# stabilizer_current_sense.net
KiCad netlist of a schematic drawn in Altium Designer
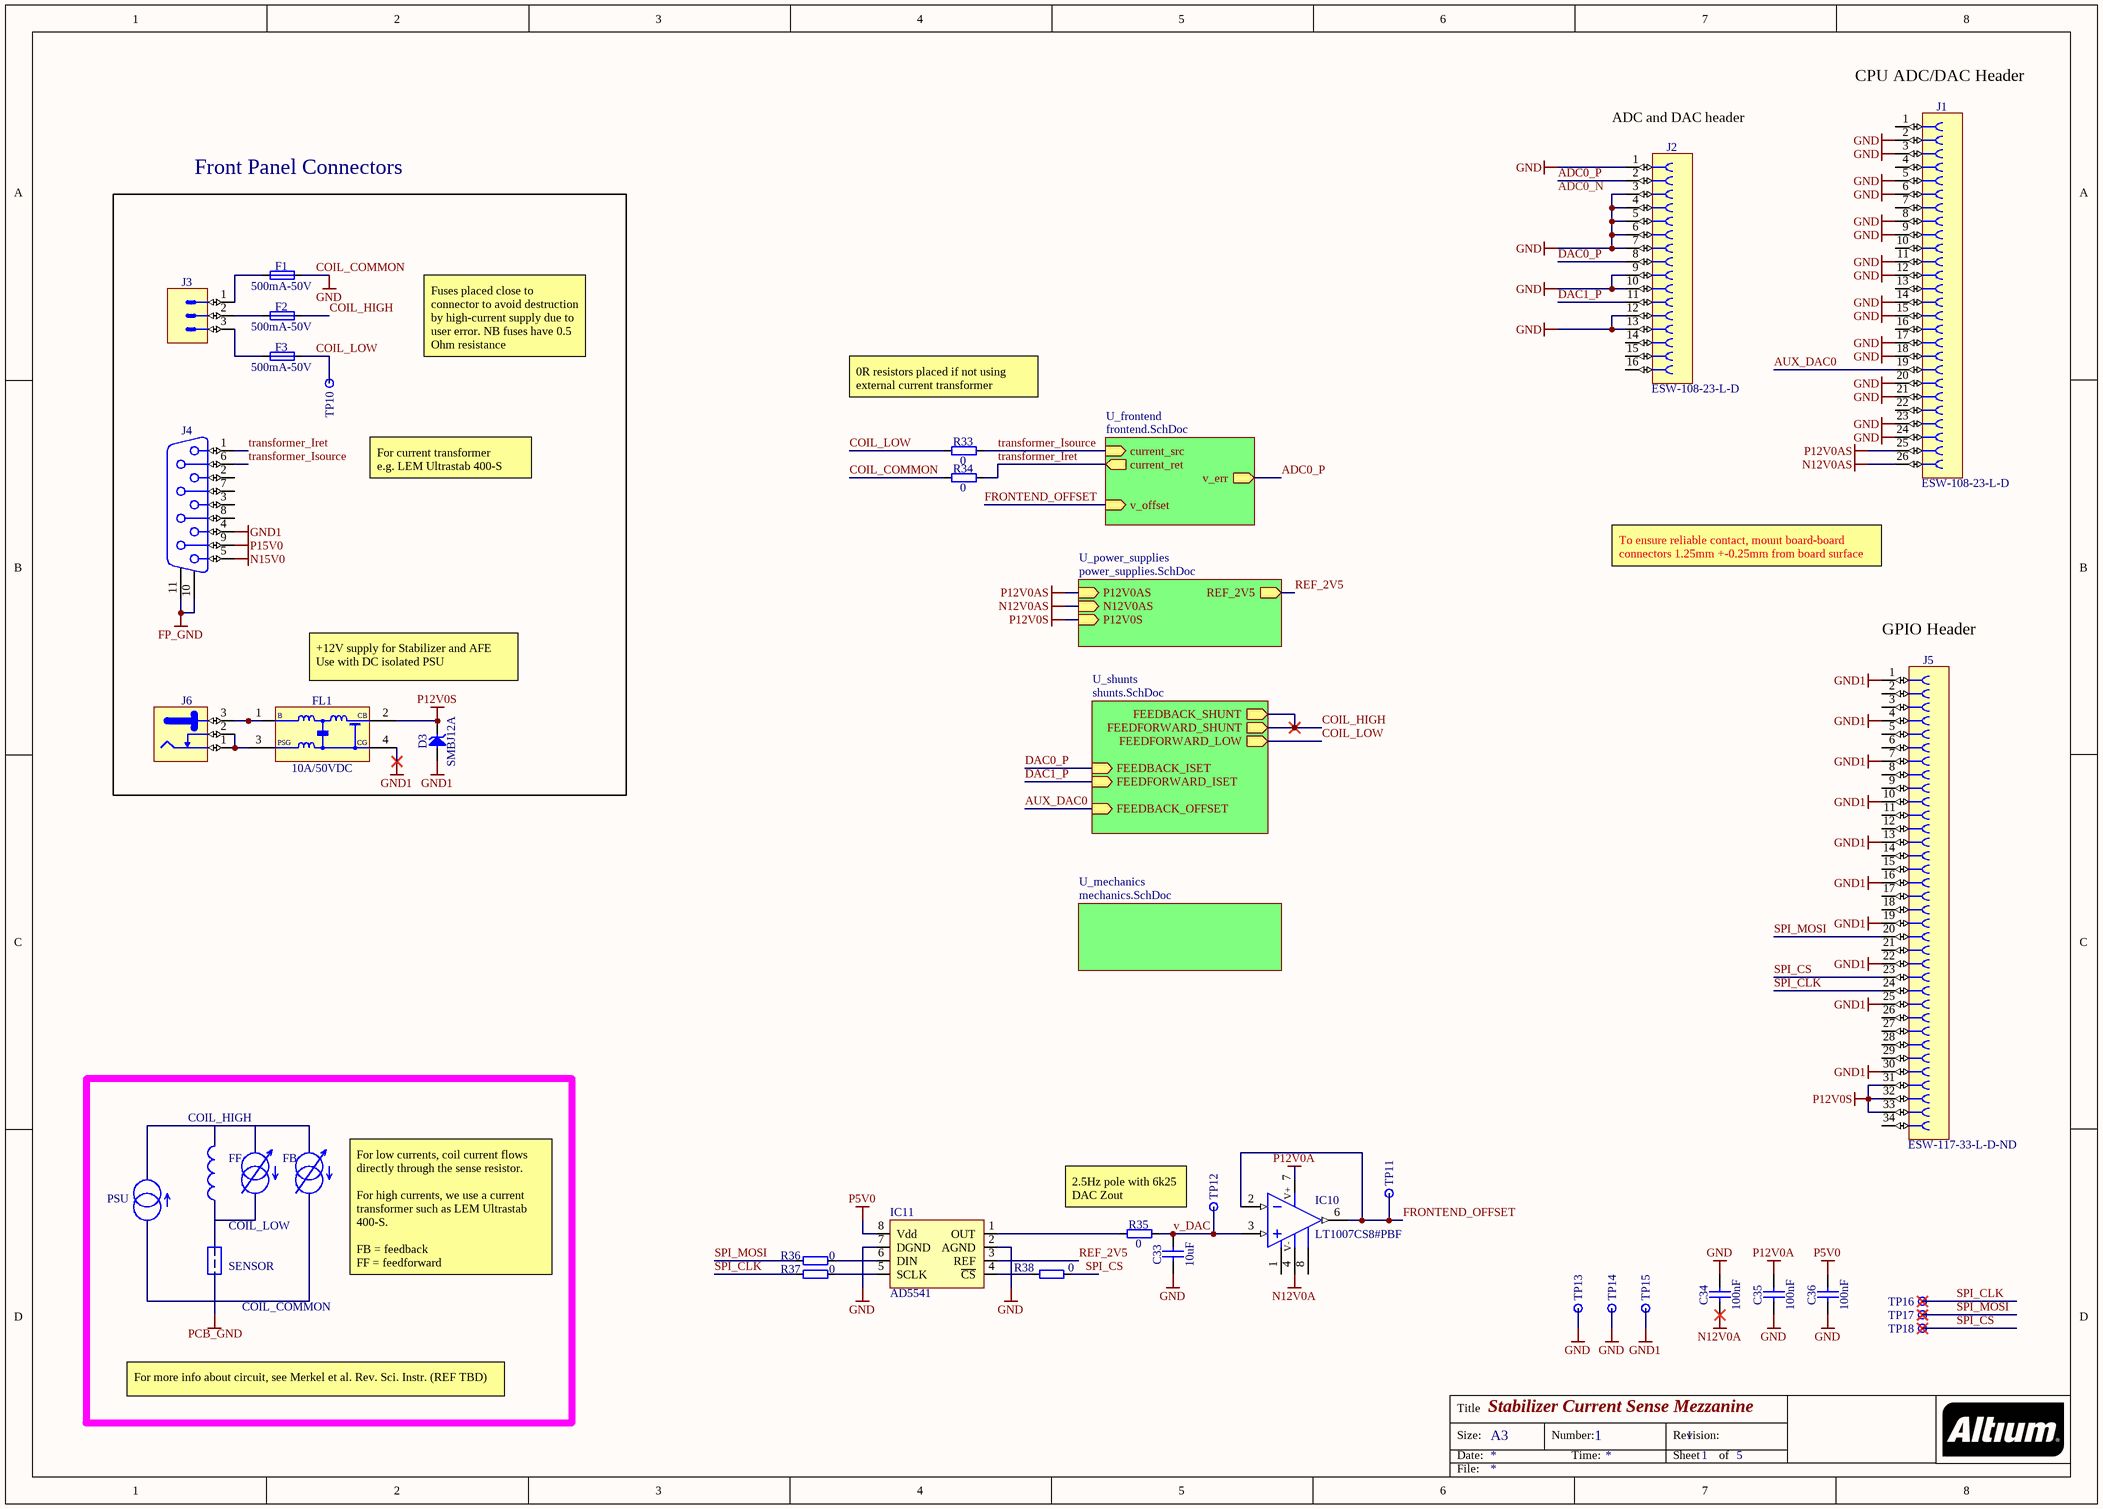
[diagram p0: stabilizer_current_sense.SchDoc]

(export (version "E")
  (design (tool "Eeschema 10.0.6"))
  (components
    (comp (ref "C33")
      (value "10uF")
      (footprint "CAPC2012X95N")
      (description "Non-polarised capacitor")
      (fields
        (field (name "PART NUMBER") "CC0805_10UF_25V_10%_X5R")
        (field (name "VOLTAGE") "25V")
        (field (name "AUTHOR") "CERN DEM JLC")
      )
      (libsource (lib "Capacitors") (part "Capacitor - non polarized"))
    )
    (comp (ref "C34")
      (value "100nF")
      (footprint "CAPC1608X87N")
      (description "Non-polarised capacitor")
      (fields
        (field (name "PART NUMBER") "CC0603_100NF_50V_10%_X7R")
        (field (name "VOLTAGE") "50V")
        (field (name "AUTHOR") "CERN DEM JLC")
      )
      (libsource (lib "Capacitors") (part "Capacitor - non polarized"))
    )
    (comp (ref "C35")
      (value "100nF")
      (footprint "CAPC1608X87N")
      (description "Non-polarised capacitor")
      (fields
        (field (name "PART NUMBER") "CC0603_100NF_50V_10%_X7R")
        (field (name "VOLTAGE") "50V")
        (field (name "AUTHOR") "CERN DEM JLC")
      )
      (libsource (lib "Capacitors") (part "Capacitor - non polarized"))
    )
    (comp (ref "C36")
      (value "100nF")
      (footprint "CAPC1608X87N")
      (description "Non-polarised capacitor")
      (fields
        (field (name "PART NUMBER") "CC0603_100NF_50V_10%_X7R")
        (field (name "VOLTAGE") "50V")
        (field (name "AUTHOR") "CERN DEM JLC")
      )
      (libsource (lib "Capacitors") (part "Capacitor - non polarized"))
    )
    (comp (ref "D3")
      (value "SMBJ12A")
      (footprint "DIOM5336X265N")
      (description "Zener Diode")
      (fields
        (field (name "VOLTAGE") "12V")
        (field (name "POWER") "600W")
        (field (name "AUTHOR") "CERN DEM JLC")
      )
      (libsource (lib "ICs And Semiconductors") (part "Diode Zener"))
    )
    (comp (ref "F1")
      (value "500mA-50V")
      (footprint "FUSC1608X55N")
      (description "Fuse")
      (fields
        (field (name "PART NUMBER") "FUS0603_BOURNS-SF-0603F050-2")
        (field (name "MANUFACTURER") "BOURNS")
        (field (name "AUTHOR") "CERN DEM JLC")
      )
      (libsource (lib "Eletro-mechanical") (part "Fuse"))
    )
    (comp (ref "F2")
      (value "500mA-50V")
      (footprint "FUSC1608X55N")
      (description "Fuse")
      (fields
        (field (name "PART NUMBER") "FUS0603_BOURNS-SF-0603F050-2")
        (field (name "MANUFACTURER") "BOURNS")
        (field (name "AUTHOR") "CERN DEM JLC")
      )
      (libsource (lib "Eletro-mechanical") (part "Fuse"))
    )
    (comp (ref "F3")
      (value "500mA-50V")
      (footprint "FUSC1608X55N")
      (description "Fuse")
      (fields
        (field (name "PART NUMBER") "FUS0603_BOURNS-SF-0603F050-2")
        (field (name "MANUFACTURER") "BOURNS")
        (field (name "AUTHOR") "CERN DEM JLC")
      )
      (libsource (lib "Eletro-mechanical") (part "Fuse"))
    )
    (comp (ref "FL1")
      (value "10A/50VDC")
      (footprint "FIL_MURATA_BNX02")
      (description "Block Type EMIFIL (LC Combined)")
      (fields
        (field (name "PART NUMBER") "FIL_MURATA_BNX022-01L")
        (field (name "MANUFACTURER") "MURATA")
        (field (name "AUTHOR") "CERN DEM JLC")
      )
      (libsource (lib "Inductors & Transformers") (part "FIL_MURATA_BNX02"))
    )
    (comp (ref "IC10")
      (value "LT1007CS8#PBF")
      (footprint "SOIC127P600X175-8N")
      (description "Operational Amplifier with Offset 1-8")
      (fields (field (name "MANUFACTURER") "LINEAR TECHNOLOGY") (field (name "AUTHOR") "CERN DEM JLC"))
      (libsource (lib "ICs And Semiconductors") (part "Operational Amplifier Type3"))
    )
    (comp (ref "IC11")
      (value "AD5541")
      (footprint "library_ICs:so-8")
      (description "16 bit serial DAC")
      (fields
        (field (name "MANUFACTURER") "ANALOG DEVICES")
        (field (name "MANUFACTURER PART NUMBER") "AD5541LRZ")
      )
      (libsource (lib "LIBRARY_SCH") (part "AD5541LRZ"))
    )
    (comp (ref "J1")
      (value "ESW-108-23-L-D")
      (footprint "connectors:ESW-113-23-L-D")
      (description "Connector Elevated Socket 26 POS 2.54mm, 13.59mm height")
      (fields
        (field (name "MANUFACTURER") "Samtec")
        (field (name "MANUFACTURER PART NUMBER") "ESW-108-23-L-D")
      )
      (libsource (lib "connectors") (part "ESW-113-23-L-D"))
    )
    (comp (ref "J2")
      (value "ESW-108-23-L-D")
      (footprint "connectors:ESW-108-23-L-D")
      (description "Connector Elevated Socket 16 POS 2.54mm, 13.59mm height")
      (fields
        (field (name "MANUFACTURER") "Samtec")
        (field (name "MANUFACTURER PART NUMBER") "ESW-108-23-L-D")
      )
      (libsource (lib "connectors") (part "ESW-108-23-L-D"))
    )
    (comp (ref "J3")
      (value "MSTBA")
      (footprint "PHOENIX_1757255")
      (description "Connector 3 Male")
      (fields
        (field (name "PART NUMBER") "PHOENIX_1757255")
        (field (name "MANUFACTURER") "PHOENIX CONTACT")
        (field (name "AUTHOR") "CERN DEM JLC")
      )
      (libsource (lib "Connectors") (part "Connector 3 Male"))
    )
    (comp (ref "J4")
      (value "D-Sub 9F")
      (footprint "FCI_D09S13A4GV00LF")
      (description "Connector D-sub 9 Female")
      (fields
        (field (name "PART NUMBER") "FCI_D09S13A4GV00LF")
        (field (name "MANUFACTURER") "FCI")
        (field (name "AUTHOR") "CERN DEM JLC")
      )
      (libsource (lib "Connectors") (part "Connector D-sub 9 Female"))
    )
    (comp (ref "J5")
      (value "ESW-108-23-L-D")
      (footprint "connectors:ESW-117-23-L-D")
      (description "Connector Elevated Socket 34 POS 2.54mm, 13.59mm height")
      (fields
        (field (name "MANUFACTURER") "Samtec")
        (field (name "MANUFACTURER PART NUMBER") "ESW-117-33-L-D-ND")
      )
      (libsource (lib "connectors") (part "ESW-117-23-L-D"))
    )
    (comp (ref "J6")
      (value "Jack")
      (footprint "Library-connectors:SWITCHCRAFT_L712RA")
      (description "24V /3. 5A, 2.1mm Diameter Pin, SMD DC Power Supply Connector With  Break Contact")
      (fields
        (field (name "PART NUMBER") "SWITCHCRAFT_L712RA")
        (field (name "MANUFACTURER") "SWITCHCRAFT")
        (field (name "AUTHOR") "GK")
      )
      (libsource (lib "LIBRARY_SCH") (part "CON_DC_5A_THT_RA"))
    )
    (comp (ref "R33")
      (value "0")
      (footprint "RESC1608X55N")
      (description "Resistor")
      (fields
        (field (name "PART NUMBER") "R0603_0R_JUMPER")
        (field (name "MANUFACTURER") "GENERIC")
        (field (name "AUTHOR") "CERN DEM JLC")
      )
      (libsource (lib "Resistors") (part "Resistor"))
    )
    (comp (ref "R34")
      (value "0")
      (footprint "RESC1608X55N")
      (description "Resistor")
      (fields
        (field (name "PART NUMBER") "R0603_0R_JUMPER")
        (field (name "MANUFACTURER") "GENERIC")
        (field (name "AUTHOR") "CERN DEM JLC")
      )
      (libsource (lib "Resistors") (part "Resistor"))
    )
    (comp (ref "R35")
      (value "0")
      (footprint "RESC1608X55N")
      (description "Resistor")
      (fields
        (field (name "PART NUMBER") "R0603_0R_JUMPER")
        (field (name "MANUFACTURER") "GENERIC")
        (field (name "AUTHOR") "CERN DEM JLC")
      )
      (libsource (lib "Resistors") (part "Resistor"))
    )
    (comp (ref "R36")
      (value "0")
      (footprint "RESC1608X55N")
      (description "Resistor")
      (fields
        (field (name "PART NUMBER") "R0603_0R_JUMPER")
        (field (name "MANUFACTURER") "GENERIC")
        (field (name "AUTHOR") "CERN DEM JLC")
      )
      (libsource (lib "Resistors") (part "Resistor"))
    )
    (comp (ref "R37")
      (value "0")
      (footprint "RESC1608X55N")
      (description "Resistor")
      (fields
        (field (name "PART NUMBER") "R0603_0R_JUMPER")
        (field (name "MANUFACTURER") "GENERIC")
        (field (name "AUTHOR") "CERN DEM JLC")
      )
      (libsource (lib "Resistors") (part "Resistor"))
    )
    (comp (ref "R38")
      (value "0")
      (footprint "RESC1608X55N")
      (description "Resistor")
      (fields
        (field (name "PART NUMBER") "R0603_0R_JUMPER")
        (field (name "MANUFACTURER") "GENERIC")
        (field (name "AUTHOR") "CERN DEM JLC")
      )
      (libsource (lib "Resistors") (part "Resistor"))
    )
    (comp (ref "TP10")
      (value "Test Point")
      (footprint "TPS127")
      (fields (field (name "PART NUMBER") "SMD_PAD_1.27X1.27MM") (field (name "AUTHOR") "CERN DEM JLC"))
      (libsource (lib "Eletro-mechanical") (part "Test Point"))
    )
    (comp (ref "TP11")
      (value "Test Point")
      (footprint "TPS127")
      (fields (field (name "PART NUMBER") "SMD_PAD_1.27X1.27MM") (field (name "AUTHOR") "CERN DEM JLC"))
      (libsource (lib "Eletro-mechanical") (part "Test Point"))
    )
    (comp (ref "TP12")
      (value "Test Point")
      (footprint "TPS127")
      (fields (field (name "PART NUMBER") "SMD_PAD_1.27X1.27MM") (field (name "AUTHOR") "CERN DEM JLC"))
      (libsource (lib "Eletro-mechanical") (part "Test Point"))
    )
    (comp (ref "TP13")
      (value "Test Point")
      (footprint "TPS127")
      (fields (field (name "PART NUMBER") "SMD_PAD_1.27X1.27MM") (field (name "AUTHOR") "CERN DEM JLC"))
      (libsource (lib "Eletro-mechanical") (part "Test Point"))
    )
    (comp (ref "TP14")
      (value "Test Point")
      (footprint "TPS127")
      (fields (field (name "PART NUMBER") "SMD_PAD_1.27X1.27MM") (field (name "AUTHOR") "CERN DEM JLC"))
      (libsource (lib "Eletro-mechanical") (part "Test Point"))
    )
    (comp (ref "TP15")
      (value "Test Point")
      (footprint "TPS127")
      (fields (field (name "PART NUMBER") "SMD_PAD_1.27X1.27MM") (field (name "AUTHOR") "CERN DEM JLC"))
      (libsource (lib "Eletro-mechanical") (part "Test Point"))
    )
    (comp (ref "TP16")
      (value "Test Point")
      (footprint "TPS127")
      (fields (field (name "PART NUMBER") "SMD_PAD_1.27X1.27MM") (field (name "AUTHOR") "CERN DEM JLC"))
      (libsource (lib "Eletro-mechanical") (part "Test Point"))
    )
    (comp (ref "TP17")
      (value "Test Point")
      (footprint "TPS127")
      (fields (field (name "PART NUMBER") "SMD_PAD_1.27X1.27MM") (field (name "AUTHOR") "CERN DEM JLC"))
      (libsource (lib "Eletro-mechanical") (part "Test Point"))
    )
    (comp (ref "TP18")
      (value "Test Point")
      (footprint "TPS127")
      (fields (field (name "PART NUMBER") "SMD_PAD_1.27X1.27MM") (field (name "AUTHOR") "CERN DEM JLC"))
      (libsource (lib "Eletro-mechanical") (part "Test Point"))
    )
  )
  (nets
    (net (code "1") (name "/ADC0_P") (class "Default")
      (node (ref "J2") (pin "2") (pinfunction "2_2") (pintype "bidirectional"))
    )
    (net (code "2") (name "/AUX_DAC0") (class "Default")
      (node (ref "J1") (pin "19") (pinfunction "19_19") (pintype "bidirectional"))
    )
    (net (code "3") (name "/COIL_HIGH") (class "Default")
      (node (ref "F2") (pin "1") (pinfunction "1_1") (pintype "passive+no_connect"))
    )
    (net (code "4") (name "/COIL_LOW") (class "Default")
      (node (ref "F3") (pin "1") (pinfunction "1_1") (pintype "passive"))
      (node (ref "R33") (pin "1") (pinfunction "1_1") (pintype "passive"))
      (node (ref "TP10") (pin "1") (pinfunction "1_1") (pintype "bidirectional"))
    )
    (net (code "5") (name "/DAC0_P") (class "Default")
      (node (ref "J2") (pin "8") (pinfunction "8_8") (pintype "bidirectional"))
    )
    (net (code "6") (name "/DAC1_P") (class "Default")
      (node (ref "J2") (pin "11") (pinfunction "11_11") (pintype "bidirectional"))
    )
    (net (code "7") (name "/FRONTEND_OFFSET") (class "Default")
      (node (ref "IC10") (pin "2") (pinfunction "IN-_2") (pintype "input"))
      (node (ref "IC10") (pin "6") (pinfunction "OUT_6") (pintype "output"))
      (node (ref "TP11") (pin "1") (pinfunction "1_1") (pintype "bidirectional"))
    )
    (net (code "8") (name "/REF_2V5") (class "Default")
      (node (ref "IC11") (pin "3") (pinfunction "REF_3") (pintype "passive"))
    )
    (net (code "9") (name "/SPI_CLK") (class "Default")
      (node (ref "J5") (pin "24") (pinfunction "24_24") (pintype "bidirectional"))
      (node (ref "R37") (pin "1") (pinfunction "1_1") (pintype "passive"))
      (node (ref "TP16") (pin "1") (pinfunction "1_1") (pintype "bidirectional"))
    )
    (net (code "10") (name "/SPI_CS") (class "Default")
      (node (ref "J5") (pin "23") (pinfunction "23_23") (pintype "bidirectional"))
      (node (ref "R38") (pin "2") (pinfunction "2_2") (pintype "passive"))
      (node (ref "TP18") (pin "1") (pinfunction "1_1") (pintype "bidirectional"))
    )
    (net (code "11") (name "/SPI_MOSI") (class "Default")
      (node (ref "J5") (pin "20") (pinfunction "20_20") (pintype "bidirectional"))
      (node (ref "R36") (pin "1") (pinfunction "1_1") (pintype "passive"))
      (node (ref "TP17") (pin "1") (pinfunction "1_1") (pintype "bidirectional"))
    )
    (net (code "12") (name "/transformer_Iret") (class "Default")
      (node (ref "J4") (pin "1") (pinfunction "1_1") (pintype "bidirectional"))
      (node (ref "R34") (pin "2") (pinfunction "2_2") (pintype "passive"))
    )
    (net (code "13") (name "/transformer_Isource") (class "Default")
      (node (ref "J4") (pin "6") (pinfunction "6_6") (pintype "bidirectional"))
      (node (ref "R33") (pin "2") (pinfunction "2_2") (pintype "passive"))
    )
    (net (code "14") (name "/v_DAC") (class "Default")
      (node (ref "C33") (pin "2") (pinfunction "2_2") (pintype "passive"))
      (node (ref "IC10") (pin "3") (pinfunction "IN+_3") (pintype "input"))
      (node (ref "R35") (pin "2") (pinfunction "2_2") (pintype "passive"))
      (node (ref "TP12") (pin "1") (pinfunction "1_1") (pintype "bidirectional"))
    )
    (net (code "15") (name "FP_GND") (class "Default")
      (node (ref "J4") (pin "10") (pinfunction "10_10") (pintype "passive"))
      (node (ref "J4") (pin "11") (pinfunction "11_11") (pintype "passive"))
    )
    (net (code "16") (name "GND") (class "Default")
      (node (ref "C33") (pin "1") (pinfunction "1_1") (pintype "passive"))
      (node (ref "C34") (pin "2") (pinfunction "2_2") (pintype "passive"))
      (node (ref "C35") (pin "1") (pinfunction "1_1") (pintype "passive"))
      (node (ref "C36") (pin "1") (pinfunction "1_1") (pintype "passive"))
      (node (ref "F1") (pin "1") (pinfunction "1_1") (pintype "passive"))
      (node (ref "IC11") (pin "2") (pinfunction "AGND_2") (pintype "passive"))
      (node (ref "IC11") (pin "7") (pinfunction "DGND_7") (pintype "passive"))
      (node (ref "J1") (pin "11") (pinfunction "11_11") (pintype "bidirectional"))
      (node (ref "J1") (pin "12") (pinfunction "12_12") (pintype "bidirectional"))
      (node (ref "J1") (pin "14") (pinfunction "14_14") (pintype "bidirectional"))
      (node (ref "J1") (pin "15") (pinfunction "15_15") (pintype "bidirectional"))
      (node (ref "J1") (pin "17") (pinfunction "17_17") (pintype "bidirectional"))
      (node (ref "J1") (pin "18") (pinfunction "18_18") (pintype "bidirectional"))
      (node (ref "J1") (pin "2") (pinfunction "2_2") (pintype "bidirectional"))
      (node (ref "J1") (pin "20") (pinfunction "20_20") (pintype "bidirectional"))
      (node (ref "J1") (pin "21") (pinfunction "21_21") (pintype "bidirectional"))
      (node (ref "J1") (pin "23") (pinfunction "23_23") (pintype "bidirectional"))
      (node (ref "J1") (pin "24") (pinfunction "24_24") (pintype "bidirectional"))
      (node (ref "J1") (pin "3") (pinfunction "3_3") (pintype "bidirectional"))
      (node (ref "J1") (pin "5") (pinfunction "5_5") (pintype "bidirectional"))
      (node (ref "J1") (pin "6") (pinfunction "6_6") (pintype "bidirectional"))
      (node (ref "J1") (pin "8") (pinfunction "8_8") (pintype "bidirectional"))
      (node (ref "J1") (pin "9") (pinfunction "9_9") (pintype "bidirectional"))
      (node (ref "J2") (pin "1") (pinfunction "1_1") (pintype "bidirectional"))
      (node (ref "J2") (pin "10") (pinfunction "10_10") (pintype "bidirectional"))
      (node (ref "J2") (pin "12") (pinfunction "12_12") (pintype "bidirectional"))
      (node (ref "J2") (pin "13") (pinfunction "13_13") (pintype "bidirectional"))
      (node (ref "J2") (pin "3") (pinfunction "3_3") (pintype "bidirectional"))
      (node (ref "J2") (pin "4") (pinfunction "4_4") (pintype "bidirectional"))
      (node (ref "J2") (pin "5") (pinfunction "5_5") (pintype "bidirectional"))
      (node (ref "J2") (pin "6") (pinfunction "6_6") (pintype "bidirectional"))
      (node (ref "J2") (pin "7") (pinfunction "7_7") (pintype "bidirectional"))
      (node (ref "J2") (pin "9") (pinfunction "9_9") (pintype "bidirectional"))
      (node (ref "R34") (pin "1") (pinfunction "1_1") (pintype "passive"))
      (node (ref "TP13") (pin "1") (pinfunction "1_1") (pintype "bidirectional"))
      (node (ref "TP14") (pin "1") (pinfunction "1_1") (pintype "bidirectional"))
    )
    (net (code "17") (name "GND1") (class "Default")
      (node (ref "D3") (pin "2") (pinfunction "A_2") (pintype "passive"))
      (node (ref "FL1") (pin "4") (pinfunction "CG_4") (pintype "passive"))
      (node (ref "J4") (pin "4") (pinfunction "4_4") (pintype "bidirectional"))
      (node (ref "J5") (pin "1") (pinfunction "1_1") (pintype "bidirectional"))
      (node (ref "J5") (pin "10") (pinfunction "10_10") (pintype "bidirectional"))
      (node (ref "J5") (pin "13") (pinfunction "13_13") (pintype "bidirectional"))
      (node (ref "J5") (pin "16") (pinfunction "16_16") (pintype "bidirectional"))
      (node (ref "J5") (pin "19") (pinfunction "19_19") (pintype "bidirectional"))
      (node (ref "J5") (pin "22") (pinfunction "22_22") (pintype "bidirectional"))
      (node (ref "J5") (pin "25") (pinfunction "25_25") (pintype "bidirectional"))
      (node (ref "J5") (pin "30") (pinfunction "30_30") (pintype "bidirectional"))
      (node (ref "J5") (pin "4") (pinfunction "4_4") (pintype "bidirectional"))
      (node (ref "J5") (pin "7") (pinfunction "7_7") (pintype "bidirectional"))
      (node (ref "TP15") (pin "1") (pinfunction "1_1") (pintype "bidirectional"))
    )
    (net (code "18") (name "N12V0A") (class "Default")
      (node (ref "C34") (pin "1") (pinfunction "1_1") (pintype "passive"))
      (node (ref "IC10") (pin "4") (pinfunction "V-_4") (pintype "power_in"))
    )
    (net (code "19") (name "N12V0AS") (class "Default")
      (node (ref "J1") (pin "26") (pinfunction "26_26") (pintype "bidirectional"))
    )
    (net (code "20") (name "N15V0") (class "Default")
      (node (ref "J4") (pin "5") (pinfunction "5_5") (pintype "bidirectional"))
    )
    (net (code "21") (name "Net-(F1-Pad2)") (class "Default")
      (node (ref "F1") (pin "2") (pinfunction "2_2") (pintype "passive"))
      (node (ref "J3") (pin "1") (pinfunction "1_1") (pintype "bidirectional"))
    )
    (net (code "22") (name "Net-(F2-Pad2)") (class "Default")
      (node (ref "F2") (pin "2") (pinfunction "2_2") (pintype "passive"))
      (node (ref "J3") (pin "2") (pinfunction "2_2") (pintype "bidirectional"))
    )
    (net (code "23") (name "Net-(F3-Pad2)") (class "Default")
      (node (ref "F3") (pin "2") (pinfunction "2_2") (pintype "passive"))
      (node (ref "J3") (pin "3") (pinfunction "3_3") (pintype "bidirectional"))
    )
    (net (code "24") (name "Net-(FL1-B)") (class "Default")
      (node (ref "FL1") (pin "1") (pinfunction "B_1") (pintype "passive"))
      (node (ref "J6") (pin "3") (pinfunction "3_3") (pintype "bidirectional"))
    )
    (net (code "25") (name "Net-(FL1-PSG)") (class "Default")
      (node (ref "FL1") (pin "3") (pinfunction "PSG_3") (pintype "passive"))
      (node (ref "J6") (pin "1") (pinfunction "1_1") (pintype "bidirectional"))
      (node (ref "J6") (pin "2") (pinfunction "2_2") (pintype "bidirectional"))
    )
    (net (code "26") (name "Net-(IC11-DIN)") (class "Default")
      (node (ref "IC11") (pin "6") (pinfunction "DIN_6") (pintype "passive"))
      (node (ref "R36") (pin "2") (pinfunction "2_2") (pintype "passive"))
    )
    (net (code "27") (name "Net-(IC11-OUT)") (class "Default")
      (node (ref "IC11") (pin "1") (pinfunction "OUT_1") (pintype "passive"))
      (node (ref "R35") (pin "1") (pinfunction "1_1") (pintype "passive"))
    )
    (net (code "28") (name "Net-(IC11-SCLK)") (class "Default")
      (node (ref "IC11") (pin "5") (pinfunction "SCLK_5") (pintype "passive"))
      (node (ref "R37") (pin "2") (pinfunction "2_2") (pintype "passive"))
    )
    (net (code "29") (name "Net-(IC11-~{CS})") (class "Default")
      (node (ref "IC11") (pin "4") (pinfunction "~{CS}_4") (pintype "passive"))
      (node (ref "R38") (pin "1") (pinfunction "1_1") (pintype "passive"))
    )
    (net (code "30") (name "P5V0") (class "Default")
      (node (ref "C36") (pin "2") (pinfunction "2_2") (pintype "passive"))
      (node (ref "IC11") (pin "8") (pinfunction "Vdd_8") (pintype "passive"))
    )
    (net (code "31") (name "P12V0A") (class "Default")
      (node (ref "C35") (pin "2") (pinfunction "2_2") (pintype "passive"))
      (node (ref "IC10") (pin "7") (pinfunction "V+_7") (pintype "power_in"))
    )
    (net (code "32") (name "P12V0AS") (class "Default")
      (node (ref "J1") (pin "25") (pinfunction "25_25") (pintype "bidirectional"))
    )
    (net (code "33") (name "P12V0S") (class "Default")
      (node (ref "D3") (pin "1") (pinfunction "C_1") (pintype "passive"))
      (node (ref "FL1") (pin "2") (pinfunction "CB_2") (pintype "passive"))
      (node (ref "J5") (pin "31") (pinfunction "31_31") (pintype "bidirectional"))
      (node (ref "J5") (pin "32") (pinfunction "32_32") (pintype "bidirectional"))
      (node (ref "J5") (pin "33") (pinfunction "33_33") (pintype "bidirectional"))
    )
    (net (code "34") (name "P15V0") (class "Default")
      (node (ref "J4") (pin "9") (pinfunction "9_9") (pintype "bidirectional"))
    )
    (net (code "35") (name "unconnected-(IC10-OFFSET-Pad1)") (class "Default")
      (node (ref "IC10") (pin "1") (pinfunction "OFFSET_1") (pintype "passive"))
    )
    (net (code "36") (name "unconnected-(IC10-OFFSET-Pad8)") (class "Default")
      (node (ref "IC10") (pin "8") (pinfunction "OFFSET_8") (pintype "passive"))
    )
    (net (code "37") (name "unconnected-(J1-Pad1)") (class "Default")
      (node (ref "J1") (pin "1") (pinfunction "1_1") (pintype "bidirectional"))
    )
    (net (code "38") (name "unconnected-(J1-Pad4)") (class "Default")
      (node (ref "J1") (pin "4") (pinfunction "4_4") (pintype "bidirectional"))
    )
    (net (code "39") (name "unconnected-(J1-Pad7)") (class "Default")
      (node (ref "J1") (pin "7") (pinfunction "7_7") (pintype "bidirectional"))
    )
    (net (code "40") (name "unconnected-(J1-Pad10)") (class "Default")
      (node (ref "J1") (pin "10") (pinfunction "10_10") (pintype "bidirectional"))
    )
    (net (code "41") (name "unconnected-(J1-Pad13)") (class "Default")
      (node (ref "J1") (pin "13") (pinfunction "13_13") (pintype "bidirectional"))
    )
    (net (code "42") (name "unconnected-(J1-Pad16)") (class "Default")
      (node (ref "J1") (pin "16") (pinfunction "16_16") (pintype "bidirectional"))
    )
    (net (code "43") (name "unconnected-(J1-Pad22)") (class "Default")
      (node (ref "J1") (pin "22") (pinfunction "22_22") (pintype "bidirectional"))
    )
    (net (code "44") (name "unconnected-(J2-Pad14)") (class "Default")
      (node (ref "J2") (pin "14") (pinfunction "14_14") (pintype "bidirectional"))
    )
    (net (code "45") (name "unconnected-(J2-Pad15)") (class "Default")
      (node (ref "J2") (pin "15") (pinfunction "15_15") (pintype "bidirectional"))
    )
    (net (code "46") (name "unconnected-(J2-Pad16)") (class "Default")
      (node (ref "J2") (pin "16") (pinfunction "16_16") (pintype "bidirectional"))
    )
    (net (code "47") (name "unconnected-(J4-Pad2)") (class "Default")
      (node (ref "J4") (pin "2") (pinfunction "2_2") (pintype "bidirectional"))
    )
    (net (code "48") (name "unconnected-(J4-Pad3)") (class "Default")
      (node (ref "J4") (pin "3") (pinfunction "3_3") (pintype "bidirectional"))
    )
    (net (code "49") (name "unconnected-(J4-Pad7)") (class "Default")
      (node (ref "J4") (pin "7") (pinfunction "7_7") (pintype "bidirectional"))
    )
    (net (code "50") (name "unconnected-(J4-Pad8)") (class "Default")
      (node (ref "J4") (pin "8") (pinfunction "8_8") (pintype "bidirectional"))
    )
    (net (code "51") (name "unconnected-(J5-Pad2)") (class "Default")
      (node (ref "J5") (pin "2") (pinfunction "2_2") (pintype "bidirectional"))
    )
    (net (code "52") (name "unconnected-(J5-Pad3)") (class "Default")
      (node (ref "J5") (pin "3") (pinfunction "3_3") (pintype "bidirectional"))
    )
    (net (code "53") (name "unconnected-(J5-Pad5)") (class "Default")
      (node (ref "J5") (pin "5") (pinfunction "5_5") (pintype "bidirectional"))
    )
    (net (code "54") (name "unconnected-(J5-Pad6)") (class "Default")
      (node (ref "J5") (pin "6") (pinfunction "6_6") (pintype "bidirectional"))
    )
    (net (code "55") (name "unconnected-(J5-Pad8)") (class "Default")
      (node (ref "J5") (pin "8") (pinfunction "8_8") (pintype "bidirectional"))
    )
    (net (code "56") (name "unconnected-(J5-Pad9)") (class "Default")
      (node (ref "J5") (pin "9") (pinfunction "9_9") (pintype "bidirectional"))
    )
    (net (code "57") (name "unconnected-(J5-Pad11)") (class "Default")
      (node (ref "J5") (pin "11") (pinfunction "11_11") (pintype "bidirectional"))
    )
    (net (code "58") (name "unconnected-(J5-Pad12)") (class "Default")
      (node (ref "J5") (pin "12") (pinfunction "12_12") (pintype "bidirectional"))
    )
    (net (code "59") (name "unconnected-(J5-Pad14)") (class "Default")
      (node (ref "J5") (pin "14") (pinfunction "14_14") (pintype "bidirectional"))
    )
    (net (code "60") (name "unconnected-(J5-Pad15)") (class "Default")
      (node (ref "J5") (pin "15") (pinfunction "15_15") (pintype "bidirectional"))
    )
    (net (code "61") (name "unconnected-(J5-Pad17)") (class "Default")
      (node (ref "J5") (pin "17") (pinfunction "17_17") (pintype "bidirectional"))
    )
    (net (code "62") (name "unconnected-(J5-Pad18)") (class "Default")
      (node (ref "J5") (pin "18") (pinfunction "18_18") (pintype "bidirectional"))
    )
    (net (code "63") (name "unconnected-(J5-Pad21)") (class "Default")
      (node (ref "J5") (pin "21") (pinfunction "21_21") (pintype "bidirectional"))
    )
    (net (code "64") (name "unconnected-(J5-Pad26)") (class "Default")
      (node (ref "J5") (pin "26") (pinfunction "26_26") (pintype "bidirectional"))
    )
    (net (code "65") (name "unconnected-(J5-Pad27)") (class "Default")
      (node (ref "J5") (pin "27") (pinfunction "27_27") (pintype "bidirectional"))
    )
    (net (code "66") (name "unconnected-(J5-Pad28)") (class "Default")
      (node (ref "J5") (pin "28") (pinfunction "28_28") (pintype "bidirectional"))
    )
    (net (code "67") (name "unconnected-(J5-Pad29)") (class "Default")
      (node (ref "J5") (pin "29") (pinfunction "29_29") (pintype "bidirectional"))
    )
    (net (code "68") (name "unconnected-(J5-Pad34)") (class "Default")
      (node (ref "J5") (pin "34") (pinfunction "34_34") (pintype "bidirectional"))
    )
  )
)
